# MCU.net
KiCad netlist of a schematic drawn in Altium Designer
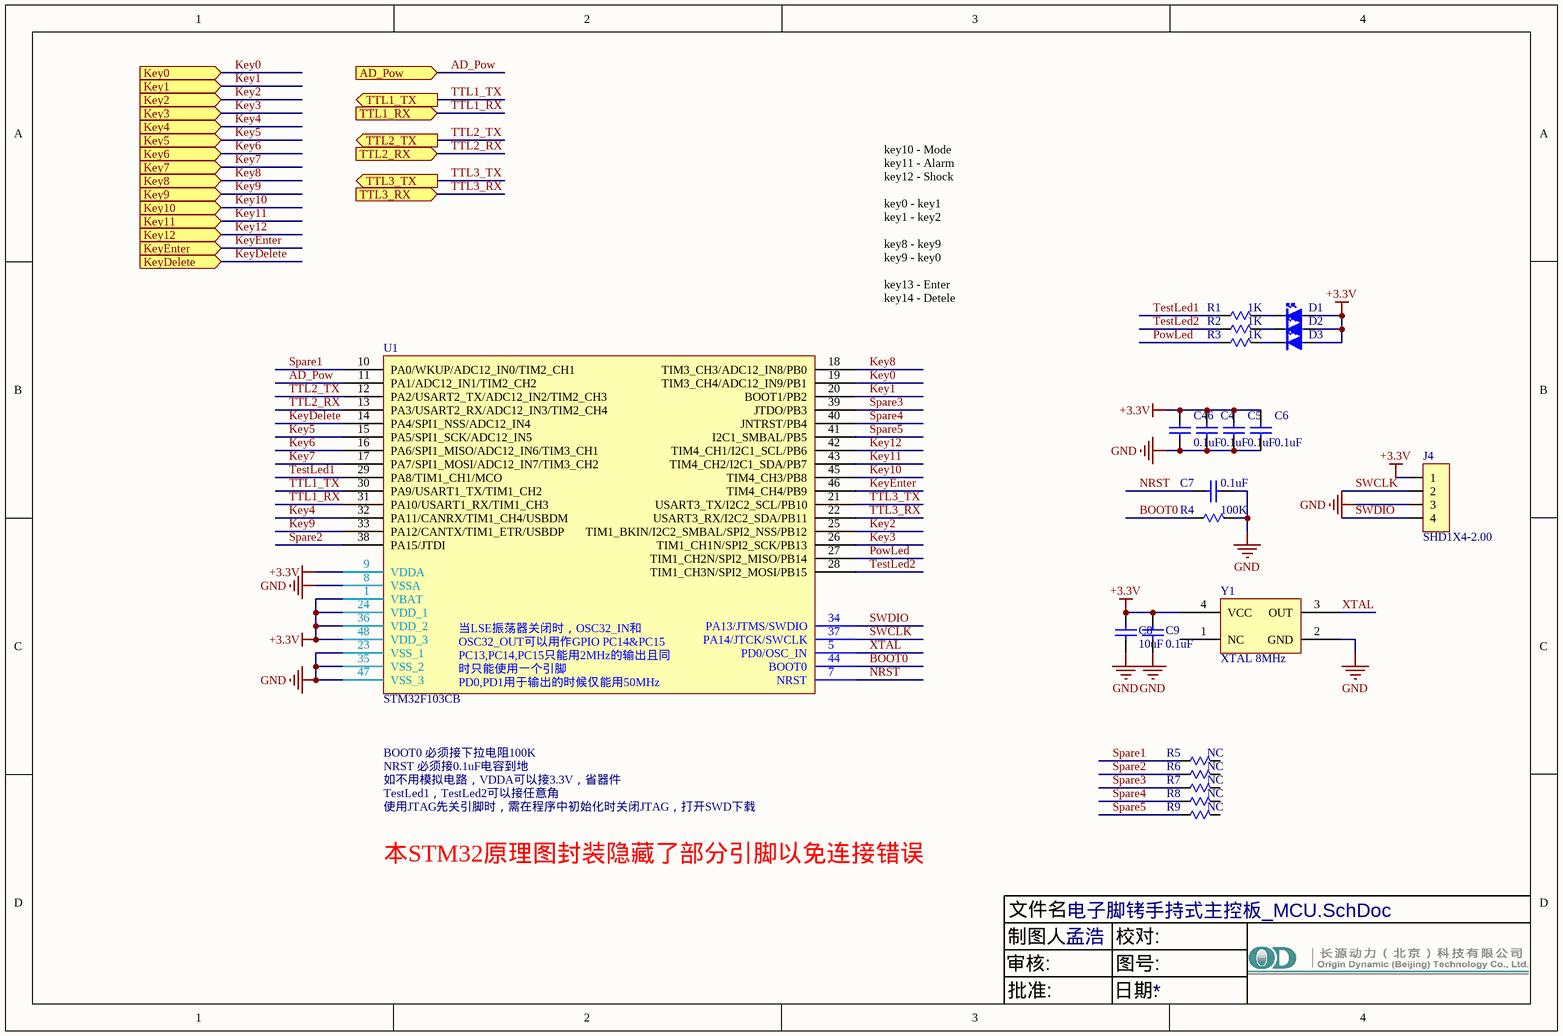
[diagram p0: 电子脚铐手持式主控板_MCU.SchDoc]

(export (version "E")
  (design (tool "Eeschema 10.0.6"))
  (components
    (comp (ref "C4")
      (value "0.1uF")
      (footprint "C0603")
      (description "CAP")
      (fields (field (name "PUBLISHER") "Altium Limited"))
      (libsource (lib "Passive Components Class") (part "CAP"))
    )
    (comp (ref "C5")
      (value "0.1uF")
      (footprint "C0603")
      (description "CAP")
      (fields (field (name "PUBLISHER") "Altium Limited"))
      (libsource (lib "Passive Components Class") (part "CAP"))
    )
    (comp (ref "C6")
      (value "0.1uF")
      (footprint "C0603")
      (description "CAP")
      (fields (field (name "PUBLISHER") "Altium Limited"))
      (libsource (lib "Passive Components Class") (part "CAP"))
    )
    (comp (ref "C7")
      (value "0.1uF")
      (footprint "C0603")
      (description "CAP")
      (fields (field (name "PUBLISHER") "Altium Limited"))
      (libsource (lib "Passive Components Class") (part "CAP"))
    )
    (comp (ref "C8")
      (value "10uF")
      (footprint "C0603")
      (description "CAP")
      (fields (field (name "PUBLISHER") "Altium Limited"))
      (libsource (lib "Passive Components Class") (part "CAP"))
    )
    (comp (ref "C9")
      (value "0.1uF")
      (footprint "C0603")
      (description "CAP")
      (fields (field (name "PUBLISHER") "Altium Limited"))
      (libsource (lib "Passive Components Class") (part "CAP"))
    )
    (comp (ref "C46")
      (value "0.1uF")
      (footprint "C0603")
      (description "CAP")
      (fields (field (name "PUBLISHER") "Altium Limited"))
      (libsource (lib "Passive Components Class") (part "CAP"))
    )
    (comp (ref "D1")
      (value "LED")
      (footprint "LED0805")
      (libsource (lib "Passive Components Class") (part "LED"))
    )
    (comp (ref "D2")
      (value "LED")
      (footprint "LED0805")
      (libsource (lib "Passive Components Class") (part "LED"))
    )
    (comp (ref "D3")
      (value "LED")
      (footprint "LED0805")
      (libsource (lib "Passive Components Class") (part "LED"))
    )
    (comp (ref "J4")
      (value "SHD1X4-2.00")
      (footprint "Jk1*4-2.0")
      (libsource (lib "Connector Class") (part "HEADER1X4"))
    )
    (comp (ref "R1")
      (value "1K")
      (footprint "R0603")
      (description "Resistor")
      (fields (field (name "PUBLISHER") "Altium Limited"))
      (libsource (lib "Passive Components Class") (part "RES"))
    )
    (comp (ref "R2")
      (value "1K")
      (footprint "R0603")
      (description "Resistor")
      (fields (field (name "PUBLISHER") "Altium Limited"))
      (libsource (lib "Passive Components Class") (part "RES"))
    )
    (comp (ref "R3")
      (value "1K")
      (footprint "R0603")
      (description "Resistor")
      (fields (field (name "PUBLISHER") "Altium Limited"))
      (libsource (lib "Passive Components Class") (part "RES"))
    )
    (comp (ref "R4")
      (value "100K")
      (footprint "R0603")
      (description "Resistor")
      (fields (field (name "PUBLISHER") "Altium Limited"))
      (libsource (lib "Passive Components Class") (part "RES"))
    )
    (comp (ref "R5")
      (value "NC")
      (footprint "R0603")
      (description "Resistor")
      (fields (field (name "PUBLISHER") "Altium Limited"))
      (libsource (lib "Passive Components Class") (part "RES"))
    )
    (comp (ref "R6")
      (value "NC")
      (footprint "R0603")
      (description "Resistor")
      (fields (field (name "PUBLISHER") "Altium Limited"))
      (libsource (lib "Passive Components Class") (part "RES"))
    )
    (comp (ref "R7")
      (value "NC")
      (footprint "R0603")
      (description "Resistor")
      (fields (field (name "PUBLISHER") "Altium Limited"))
      (libsource (lib "Passive Components Class") (part "RES"))
    )
    (comp (ref "R8")
      (value "NC")
      (footprint "R0603")
      (description "Resistor")
      (fields (field (name "PUBLISHER") "Altium Limited"))
      (libsource (lib "Passive Components Class") (part "RES"))
    )
    (comp (ref "R9")
      (value "NC")
      (footprint "R0603")
      (description "Resistor")
      (fields (field (name "PUBLISHER") "Altium Limited"))
      (libsource (lib "Passive Components Class") (part "RES"))
    )
    (comp (ref "U1")
      (value "STM32F103CB")
      (footprint "LQFP48")
      (libsource (lib "stm32") (part "STM32F103Cx"))
    )
    (comp (ref "Y1") (value "XTAL 8MHz") (footprint "XTAL5032") (libsource (lib "Mic2805") (part "XTAL")))
  )
  (nets
    (net (code "1") (name "+3.3V") (class "Default")
      (node (ref "C4") (pin "1") (pinfunction "1_1") (pintype "passive"))
      (node (ref "C46") (pin "1") (pinfunction "1_1") (pintype "passive"))
      (node (ref "C5") (pin "1") (pinfunction "1_1") (pintype "passive"))
      (node (ref "C6") (pin "1") (pinfunction "1_1") (pintype "passive"))
      (node (ref "C8") (pin "2") (pinfunction "2_2") (pintype "passive"))
      (node (ref "C9") (pin "2") (pinfunction "2_2") (pintype "passive"))
      (node (ref "D1") (pin "1") (pinfunction "A_1") (pintype "passive"))
      (node (ref "D2") (pin "1") (pinfunction "A_1") (pintype "passive"))
      (node (ref "D3") (pin "1") (pinfunction "A_1") (pintype "passive"))
      (node (ref "J4") (pin "1") (pinfunction "1_1") (pintype "passive"))
      (node (ref "U1") (pin "1") (pinfunction "VBAT_1") (pintype "power_in"))
      (node (ref "U1") (pin "24") (pinfunction "VDD_1_24") (pintype "power_in"))
      (node (ref "U1") (pin "36") (pinfunction "VDD_2_36") (pintype "power_in"))
      (node (ref "U1") (pin "48") (pinfunction "VDD_3_48") (pintype "power_in"))
      (node (ref "U1") (pin "9") (pinfunction "VDDA_9") (pintype "power_in"))
      (node (ref "Y1") (pin "4") (pinfunction "VCC_4") (pintype "passive"))
    )
    (net (code "2") (name "/AD_Pow") (class "Default")
      (node (ref "U1") (pin "11") (pinfunction "PA1/ADC12_IN1/TIM2_CH2_11") (pintype "passive"))
    )
    (net (code "3") (name "/BOOT0") (class "Default")
      (node (ref "R4") (pin "1") (pinfunction "1_1") (pintype "passive"))
      (node (ref "U1") (pin "44") (pinfunction "BOOT0_44") (pintype "passive"))
    )
    (net (code "4") (name "/Key0") (class "Default")
      (node (ref "U1") (pin "19") (pinfunction "TIM3_CH4/ADC12_IN9/PB1_19") (pintype "passive"))
    )
    (net (code "5") (name "/Key1") (class "Default")
      (node (ref "U1") (pin "20") (pinfunction "BOOT1/PB2_20") (pintype "passive"))
    )
    (net (code "6") (name "/Key2") (class "Default")
      (node (ref "U1") (pin "25") (pinfunction "TIM1_BKIN/I2C2_SMBAL/SPI2_NSS/PB12_25") (pintype "passive"))
    )
    (net (code "7") (name "/Key3") (class "Default")
      (node (ref "U1") (pin "26") (pinfunction "TIM1_CH1N/SPI2_SCK/PB13_26") (pintype "passive"))
    )
    (net (code "8") (name "/Key4") (class "Default")
      (node (ref "U1") (pin "32") (pinfunction "PA11/CANRX/TIM1_CH4/USBDM_32") (pintype "passive"))
    )
    (net (code "9") (name "/Key5") (class "Default")
      (node (ref "U1") (pin "15") (pinfunction "PA5/SPI1_SCK/ADC12_IN5_15") (pintype "passive"))
    )
    (net (code "10") (name "/Key6") (class "Default")
      (node (ref "U1") (pin "16") (pinfunction "PA6/SPI1_MISO/ADC12_IN6/TIM3_CH1_16") (pintype "passive"))
    )
    (net (code "11") (name "/Key7") (class "Default")
      (node (ref "U1") (pin "17") (pinfunction "PA7/SPI1_MOSI/ADC12_IN7/TIM3_CH2_17") (pintype "passive"))
    )
    (net (code "12") (name "/Key8") (class "Default")
      (node (ref "U1") (pin "18") (pinfunction "TIM3_CH3/ADC12_IN8/PB0_18") (pintype "passive"))
    )
    (net (code "13") (name "/Key9") (class "Default")
      (node (ref "U1") (pin "33") (pinfunction "PA12/CANTX/TIM1_ETR/USBDP_33") (pintype "passive"))
    )
    (net (code "14") (name "/Key10") (class "Default")
      (node (ref "U1") (pin "45") (pinfunction "TIM4_CH3/PB8_45") (pintype "passive"))
    )
    (net (code "15") (name "/Key11") (class "Default")
      (node (ref "U1") (pin "43") (pinfunction "TIM4_CH2/I2C1_SDA/PB7_43") (pintype "passive"))
    )
    (net (code "16") (name "/Key12") (class "Default")
      (node (ref "U1") (pin "42") (pinfunction "TIM4_CH1/I2C1_SCL/PB6_42") (pintype "passive"))
    )
    (net (code "17") (name "/KeyDelete") (class "Default")
      (node (ref "U1") (pin "14") (pinfunction "PA4/SPI1_NSS/ADC12_IN4_14") (pintype "passive"))
    )
    (net (code "18") (name "/KeyEnter") (class "Default")
      (node (ref "U1") (pin "46") (pinfunction "TIM4_CH4/PB9_46") (pintype "passive"))
    )
    (net (code "19") (name "/NRST") (class "Default")
      (node (ref "C7") (pin "1") (pinfunction "1_1") (pintype "passive"))
      (node (ref "U1") (pin "7") (pinfunction "NRST_7") (pintype "passive"))
    )
    (net (code "20") (name "/PowLed") (class "Default")
      (node (ref "R3") (pin "1") (pinfunction "1_1") (pintype "passive"))
      (node (ref "U1") (pin "27") (pinfunction "TIM1_CH2N/SPI2_MISO/PB14_27") (pintype "passive"))
    )
    (net (code "21") (name "/SWCLK") (class "Default")
      (node (ref "J4") (pin "2") (pinfunction "2_2") (pintype "passive"))
      (node (ref "U1") (pin "37") (pinfunction "PA14/JTCK/SWCLK_37") (pintype "passive"))
    )
    (net (code "22") (name "/SWDIO") (class "Default")
      (node (ref "J4") (pin "4") (pinfunction "4_4") (pintype "passive"))
      (node (ref "U1") (pin "34") (pinfunction "PA13/JTMS/SWDIO_34") (pintype "passive"))
    )
    (net (code "23") (name "/Spare1") (class "Default")
      (node (ref "R5") (pin "1") (pinfunction "1_1") (pintype "passive"))
      (node (ref "U1") (pin "10") (pinfunction "PA0/WKUP/ADC12_IN0/TIM2_CH1_10") (pintype "passive"))
    )
    (net (code "24") (name "/Spare2") (class "Default")
      (node (ref "R6") (pin "1") (pinfunction "1_1") (pintype "passive"))
      (node (ref "U1") (pin "38") (pinfunction "PA15/JTDI_38") (pintype "passive"))
    )
    (net (code "25") (name "/Spare3") (class "Default")
      (node (ref "R7") (pin "1") (pinfunction "1_1") (pintype "passive"))
      (node (ref "U1") (pin "39") (pinfunction "JTDO/PB3_39") (pintype "passive"))
    )
    (net (code "26") (name "/Spare4") (class "Default")
      (node (ref "R8") (pin "1") (pinfunction "1_1") (pintype "passive"))
      (node (ref "U1") (pin "40") (pinfunction "JNTRST/PB4_40") (pintype "passive"))
    )
    (net (code "27") (name "/Spare5") (class "Default")
      (node (ref "R9") (pin "1") (pinfunction "1_1") (pintype "passive"))
      (node (ref "U1") (pin "41") (pinfunction "I2C1_SMBAL/PB5_41") (pintype "passive"))
    )
    (net (code "28") (name "/TTL1_RX") (class "Default")
      (node (ref "U1") (pin "31") (pinfunction "PA10/USART1_RX/TIM1_CH3_31") (pintype "passive"))
    )
    (net (code "29") (name "/TTL1_TX") (class "Default")
      (node (ref "U1") (pin "30") (pinfunction "PA9/USART1_TX/TIM1_CH2_30") (pintype "passive"))
    )
    (net (code "30") (name "/TTL2_RX") (class "Default")
      (node (ref "U1") (pin "13") (pinfunction "PA3/USART2_RX/ADC12_IN3/TIM2_CH4_13") (pintype "passive"))
    )
    (net (code "31") (name "/TTL2_TX") (class "Default")
      (node (ref "U1") (pin "12") (pinfunction "PA2/USART2_TX/ADC12_IN2/TIM2_CH3_12") (pintype "passive"))
    )
    (net (code "32") (name "/TTL3_RX") (class "Default")
      (node (ref "U1") (pin "22") (pinfunction "USART3_RX/I2C2_SDA/PB11_22") (pintype "passive"))
    )
    (net (code "33") (name "/TTL3_TX") (class "Default")
      (node (ref "U1") (pin "21") (pinfunction "USART3_TX/I2C2_SCL/PB10_21") (pintype "passive"))
    )
    (net (code "34") (name "/TestLed1") (class "Default")
      (node (ref "R1") (pin "1") (pinfunction "1_1") (pintype "passive"))
      (node (ref "U1") (pin "29") (pinfunction "PA8/TIM1_CH1/MCO_29") (pintype "passive"))
    )
    (net (code "35") (name "/TestLed2") (class "Default")
      (node (ref "R2") (pin "1") (pinfunction "1_1") (pintype "passive"))
      (node (ref "U1") (pin "28") (pinfunction "TIM1_CH3N/SPI2_MOSI/PB15_28") (pintype "passive"))
    )
    (net (code "36") (name "/XTAL") (class "Default")
      (node (ref "U1") (pin "5") (pinfunction "PD0/OSC_IN_5") (pintype "passive"))
      (node (ref "Y1") (pin "3") (pinfunction "OUT_3") (pintype "passive"))
    )
    (net (code "37") (name "GND") (class "Default")
      (node (ref "C4") (pin "2") (pinfunction "2_2") (pintype "passive"))
      (node (ref "C46") (pin "2") (pinfunction "2_2") (pintype "passive"))
      (node (ref "C5") (pin "2") (pinfunction "2_2") (pintype "passive"))
      (node (ref "C6") (pin "2") (pinfunction "2_2") (pintype "passive"))
      (node (ref "C7") (pin "2") (pinfunction "2_2") (pintype "passive"))
      (node (ref "C8") (pin "1") (pinfunction "1_1") (pintype "passive"))
      (node (ref "C9") (pin "1") (pinfunction "1_1") (pintype "passive"))
      (node (ref "J4") (pin "3") (pinfunction "3_3") (pintype "passive"))
      (node (ref "R4") (pin "2") (pinfunction "2_2") (pintype "passive"))
      (node (ref "U1") (pin "23") (pinfunction "VSS_1_23") (pintype "power_in"))
      (node (ref "U1") (pin "35") (pinfunction "VSS_2_35") (pintype "power_in"))
      (node (ref "U1") (pin "47") (pinfunction "VSS_3_47") (pintype "power_in"))
      (node (ref "U1") (pin "8") (pinfunction "VSSA_8") (pintype "power_in"))
      (node (ref "Y1") (pin "2") (pinfunction "GND_2") (pintype "passive"))
    )
    (net (code "38") (name "Net-(D1-K)") (class "Default")
      (node (ref "D1") (pin "2") (pinfunction "K_2") (pintype "passive"))
      (node (ref "R1") (pin "2") (pinfunction "2_2") (pintype "passive"))
    )
    (net (code "39") (name "Net-(D2-K)") (class "Default")
      (node (ref "D2") (pin "2") (pinfunction "K_2") (pintype "passive"))
      (node (ref "R2") (pin "2") (pinfunction "2_2") (pintype "passive"))
    )
    (net (code "40") (name "Net-(D3-K)") (class "Default")
      (node (ref "D3") (pin "2") (pinfunction "K_2") (pintype "passive"))
      (node (ref "R3") (pin "2") (pinfunction "2_2") (pintype "passive"))
    )
    (net (code "41") (name "unconnected-(R5-Pad2)") (class "Default")
      (node (ref "R5") (pin "2") (pinfunction "2_2") (pintype "passive"))
    )
    (net (code "42") (name "unconnected-(R6-Pad2)") (class "Default")
      (node (ref "R6") (pin "2") (pinfunction "2_2") (pintype "passive"))
    )
    (net (code "43") (name "unconnected-(R7-Pad2)") (class "Default")
      (node (ref "R7") (pin "2") (pinfunction "2_2") (pintype "passive"))
    )
    (net (code "44") (name "unconnected-(R8-Pad2)") (class "Default")
      (node (ref "R8") (pin "2") (pinfunction "2_2") (pintype "passive"))
    )
    (net (code "45") (name "unconnected-(R9-Pad2)") (class "Default")
      (node (ref "R9") (pin "2") (pinfunction "2_2") (pintype "passive"))
    )
    (net (code "46") (name "unconnected-(U1-PC13-TAMPER-RTC-Pad2)") (class "Default")
      (node (ref "U1") (pin "2") (pinfunction "PC13-TAMPER-RTC_2") (pintype "passive"))
    )
    (net (code "47") (name "unconnected-(U1-PC14-OSC32_IN-Pad3)") (class "Default")
      (node (ref "U1") (pin "3") (pinfunction "PC14-OSC32_IN_3") (pintype "passive"))
    )
    (net (code "48") (name "unconnected-(U1-PC15-OSC32_OUT-Pad4)") (class "Default")
      (node (ref "U1") (pin "4") (pinfunction "PC15-OSC32_OUT_4") (pintype "passive"))
    )
    (net (code "49") (name "unconnected-(U1-PD1{slash}OSC_OUT-Pad6)") (class "Default")
      (node (ref "U1") (pin "6") (pinfunction "PD1/OSC_OUT_6") (pintype "passive"))
    )
    (net (code "50") (name "unconnected-(Y1-NC-Pad1)") (class "Default")
      (node (ref "Y1") (pin "1") (pinfunction "NC_1") (pintype "passive"))
    )
  )
)
